# adaptador_vga_scart_activo.net
KiCad netlist of a schematic drawn in EAGLE
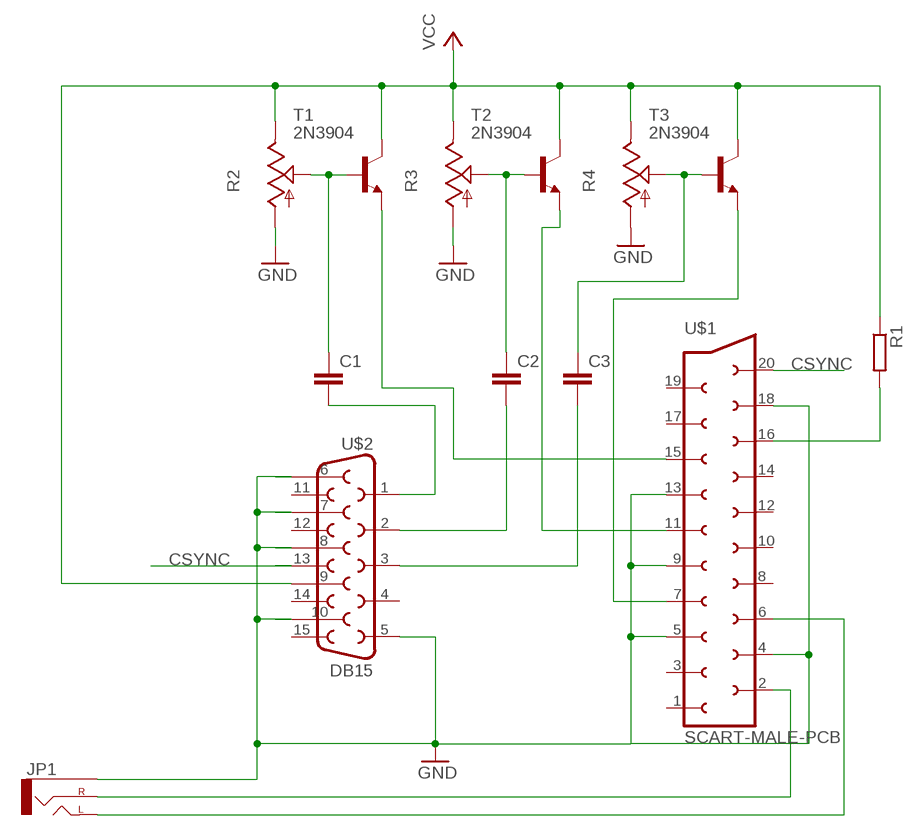
[diagram p0: schematic, sheet 1]

(export (version "E")
  (design (tool "Eeschema 10.0.6"))
  (components
    (comp (ref "C1")
      (value "C2,5-3")
      (footprint "eagle-import:C2.5-3")
      (libsource (lib "eagle-import") (part "C2,5-3"))
    )
    (comp (ref "C2")
      (value "C2,5-3")
      (footprint "eagle-import:C2.5-3")
      (libsource (lib "eagle-import") (part "C2,5-3"))
    )
    (comp (ref "C3")
      (value "C2,5-3")
      (footprint "eagle-import:C2.5-3")
      (libsource (lib "eagle-import") (part "C2,5-3"))
    )
    (comp (ref "JP1")
      (value "AUDIO-JACKPTH")
      (footprint "eagle-import:AUDIO-JACK")
      (libsource (lib "eagle-import") (part "AUDIO-JACKPTH"))
    )
    (comp (ref "R1")
      (value "R-EU_0204/5")
      (footprint "eagle-import:0204_5")
      (libsource (lib "eagle-import") (part "R-EU_0204/5"))
    )
    (comp (ref "R2")
      (value "TRIM_US-CA6V")
      (footprint "eagle-import:CA6V")
      (libsource (lib "eagle-import") (part "TRIM_US-CA6V"))
    )
    (comp (ref "R3")
      (value "TRIM_US-CA6V")
      (footprint "eagle-import:CA6V")
      (libsource (lib "eagle-import") (part "TRIM_US-CA6V"))
    )
    (comp (ref "R4")
      (value "TRIM_US-CA6V")
      (footprint "eagle-import:CA6V")
      (libsource (lib "eagle-import") (part "TRIM_US-CA6V"))
    )
    (comp (ref "T1")
      (value "2N3904")
      (footprint "eagle-import:TO92")
      (libsource (lib "eagle-import") (part "2N3904"))
    )
    (comp (ref "T2")
      (value "2N3904")
      (footprint "eagle-import:TO92")
      (libsource (lib "eagle-import") (part "2N3904"))
    )
    (comp (ref "T3")
      (value "2N3904")
      (footprint "eagle-import:TO92")
      (libsource (lib "eagle-import") (part "2N3904"))
    )
    (comp (ref "U$1")
      (value "SCART-MALE-PCB")
      (footprint "eagle-import:SCART-PCB")
      (libsource (lib "eagle-import") (part "SCART-MALE-PCB"))
    )
    (comp (ref "U$2")
      (value "DB15")
      (footprint "eagle-import:DB15")
      (libsource (lib "eagle-import") (part "DB15"))
    )
  )
  (nets
    (net (code "1") (name "/CSYNC") (class "Default")
      (node (ref "U$1") (pin "20") (pinfunction "20_20") (pintype "passive"))
      (node (ref "U$2") (pin "13") (pinfunction "13_13") (pintype "passive"))
    )
    (net (code "2") (name "GND") (class "Default")
      (node (ref "JP1") (pin "SLEEVE") (pinfunction "SLEEVE_SLEEVE") (pintype "bidirectional"))
      (node (ref "R2") (pin "A") (pinfunction "A_A") (pintype "passive"))
      (node (ref "R3") (pin "A") (pinfunction "A_A") (pintype "passive"))
      (node (ref "R4") (pin "A") (pinfunction "A_A") (pintype "passive"))
      (node (ref "U$1") (pin "13") (pinfunction "13_13") (pintype "passive"))
      (node (ref "U$1") (pin "18") (pinfunction "18_18") (pintype "passive"))
      (node (ref "U$1") (pin "4") (pinfunction "4_4") (pintype "passive"))
      (node (ref "U$1") (pin "5") (pinfunction "5_5") (pintype "passive"))
      (node (ref "U$1") (pin "9") (pinfunction "9_9") (pintype "passive"))
      (node (ref "U$2") (pin "10") (pinfunction "10_10") (pintype "passive"))
      (node (ref "U$2") (pin "5") (pinfunction "5_5") (pintype "passive"))
      (node (ref "U$2") (pin "6") (pinfunction "6_6") (pintype "passive"))
      (node (ref "U$2") (pin "7") (pinfunction "7_7") (pintype "passive"))
      (node (ref "U$2") (pin "8") (pinfunction "8_8") (pintype "passive"))
    )
    (net (code "3") (name "Net-(C1-Pad2)") (class "Default")
      (node (ref "C1") (pin "2") (pinfunction "2_2") (pintype "passive"))
      (node (ref "U$2") (pin "1") (pinfunction "1_1") (pintype "passive"))
    )
    (net (code "4") (name "Net-(C2-Pad2)") (class "Default")
      (node (ref "C2") (pin "2") (pinfunction "2_2") (pintype "passive"))
      (node (ref "U$2") (pin "2") (pinfunction "2_2") (pintype "passive"))
    )
    (net (code "5") (name "Net-(C3-Pad2)") (class "Default")
      (node (ref "C3") (pin "2") (pinfunction "2_2") (pintype "passive"))
      (node (ref "U$2") (pin "3") (pinfunction "3_3") (pintype "passive"))
    )
    (net (code "6") (name "Net-(JP1-LEFT)") (class "Default")
      (node (ref "JP1") (pin "TIP") (pinfunction "LEFT_TIP") (pintype "bidirectional"))
      (node (ref "U$1") (pin "6") (pinfunction "6_6") (pintype "passive"))
    )
    (net (code "7") (name "Net-(JP1-RIGHT)") (class "Default")
      (node (ref "JP1") (pin "RING") (pinfunction "RIGHT_RING") (pintype "bidirectional"))
      (node (ref "U$1") (pin "2") (pinfunction "2_2") (pintype "passive"))
    )
    (net (code "8") (name "Net-(R1-Pad2)") (class "Default")
      (node (ref "R1") (pin "2") (pinfunction "2_2") (pintype "passive"))
      (node (ref "U$1") (pin "16") (pinfunction "16_16") (pintype "passive"))
    )
    (net (code "9") (name "Net-(T1-B)") (class "Default")
      (node (ref "C1") (pin "1") (pinfunction "1_1") (pintype "passive"))
      (node (ref "R2") (pin "S") (pinfunction "S_S") (pintype "passive"))
      (node (ref "T1") (pin "2") (pinfunction "B_2") (pintype "passive"))
    )
    (net (code "10") (name "Net-(T1-E)") (class "Default")
      (node (ref "T1") (pin "3") (pinfunction "E_3") (pintype "passive"))
      (node (ref "U$1") (pin "15") (pinfunction "15_15") (pintype "passive"))
    )
    (net (code "11") (name "Net-(T2-B)") (class "Default")
      (node (ref "C2") (pin "1") (pinfunction "1_1") (pintype "passive"))
      (node (ref "R3") (pin "S") (pinfunction "S_S") (pintype "passive"))
      (node (ref "T2") (pin "2") (pinfunction "B_2") (pintype "passive"))
    )
    (net (code "12") (name "Net-(T2-E)") (class "Default")
      (node (ref "T2") (pin "3") (pinfunction "E_3") (pintype "passive"))
      (node (ref "U$1") (pin "11") (pinfunction "11_11") (pintype "passive"))
    )
    (net (code "13") (name "Net-(T3-B)") (class "Default")
      (node (ref "C3") (pin "1") (pinfunction "1_1") (pintype "passive"))
      (node (ref "R4") (pin "S") (pinfunction "S_S") (pintype "passive"))
      (node (ref "T3") (pin "2") (pinfunction "B_2") (pintype "passive"))
    )
    (net (code "14") (name "Net-(T3-E)") (class "Default")
      (node (ref "T3") (pin "3") (pinfunction "E_3") (pintype "passive"))
      (node (ref "U$1") (pin "7") (pinfunction "7_7") (pintype "passive"))
    )
    (net (code "15") (name "VCC") (class "Default")
      (node (ref "R1") (pin "1") (pinfunction "1_1") (pintype "passive"))
      (node (ref "R2") (pin "E") (pinfunction "E_E") (pintype "passive"))
      (node (ref "R3") (pin "E") (pinfunction "E_E") (pintype "passive"))
      (node (ref "R4") (pin "E") (pinfunction "E_E") (pintype "passive"))
      (node (ref "T1") (pin "1") (pinfunction "C_1") (pintype "passive"))
      (node (ref "T2") (pin "1") (pinfunction "C_1") (pintype "passive"))
      (node (ref "T3") (pin "1") (pinfunction "C_1") (pintype "passive"))
      (node (ref "U$2") (pin "9") (pinfunction "9_9") (pintype "passive"))
    )
    (net (code "16") (name "unconnected-(U$1-Pad1)") (class "Default")
      (node (ref "U$1") (pin "1") (pinfunction "1_1") (pintype "passive"))
    )
    (net (code "17") (name "unconnected-(U$1-Pad3)") (class "Default")
      (node (ref "U$1") (pin "3") (pinfunction "3_3") (pintype "passive"))
    )
    (net (code "18") (name "unconnected-(U$1-Pad8)") (class "Default")
      (node (ref "U$1") (pin "8") (pinfunction "8_8") (pintype "passive"))
    )
    (net (code "19") (name "unconnected-(U$1-Pad10)") (class "Default")
      (node (ref "U$1") (pin "10") (pinfunction "10_10") (pintype "passive"))
    )
    (net (code "20") (name "unconnected-(U$1-Pad12)") (class "Default")
      (node (ref "U$1") (pin "12") (pinfunction "12_12") (pintype "passive"))
    )
    (net (code "21") (name "unconnected-(U$1-Pad14)") (class "Default")
      (node (ref "U$1") (pin "14") (pinfunction "14_14") (pintype "passive"))
    )
    (net (code "22") (name "unconnected-(U$1-Pad17)") (class "Default")
      (node (ref "U$1") (pin "17") (pinfunction "17_17") (pintype "passive"))
    )
    (net (code "23") (name "unconnected-(U$1-Pad19)") (class "Default")
      (node (ref "U$1") (pin "19") (pinfunction "19_19") (pintype "passive"))
    )
    (net (code "24") (name "unconnected-(U$2-Pad4)") (class "Default")
      (node (ref "U$2") (pin "4") (pinfunction "4_4") (pintype "passive"))
    )
    (net (code "25") (name "unconnected-(U$2-Pad11)") (class "Default")
      (node (ref "U$2") (pin "11") (pinfunction "11_11") (pintype "passive"))
    )
    (net (code "26") (name "unconnected-(U$2-Pad12)") (class "Default")
      (node (ref "U$2") (pin "12") (pinfunction "12_12") (pintype "passive"))
    )
    (net (code "27") (name "unconnected-(U$2-Pad14)") (class "Default")
      (node (ref "U$2") (pin "14") (pinfunction "14_14") (pintype "passive"))
    )
    (net (code "28") (name "unconnected-(U$2-Pad15)") (class "Default")
      (node (ref "U$2") (pin "15") (pinfunction "15_15") (pintype "passive"))
    )
  )
)
